# zigo_schem.net
KiCad netlist of a schematic drawn in Altium Designer
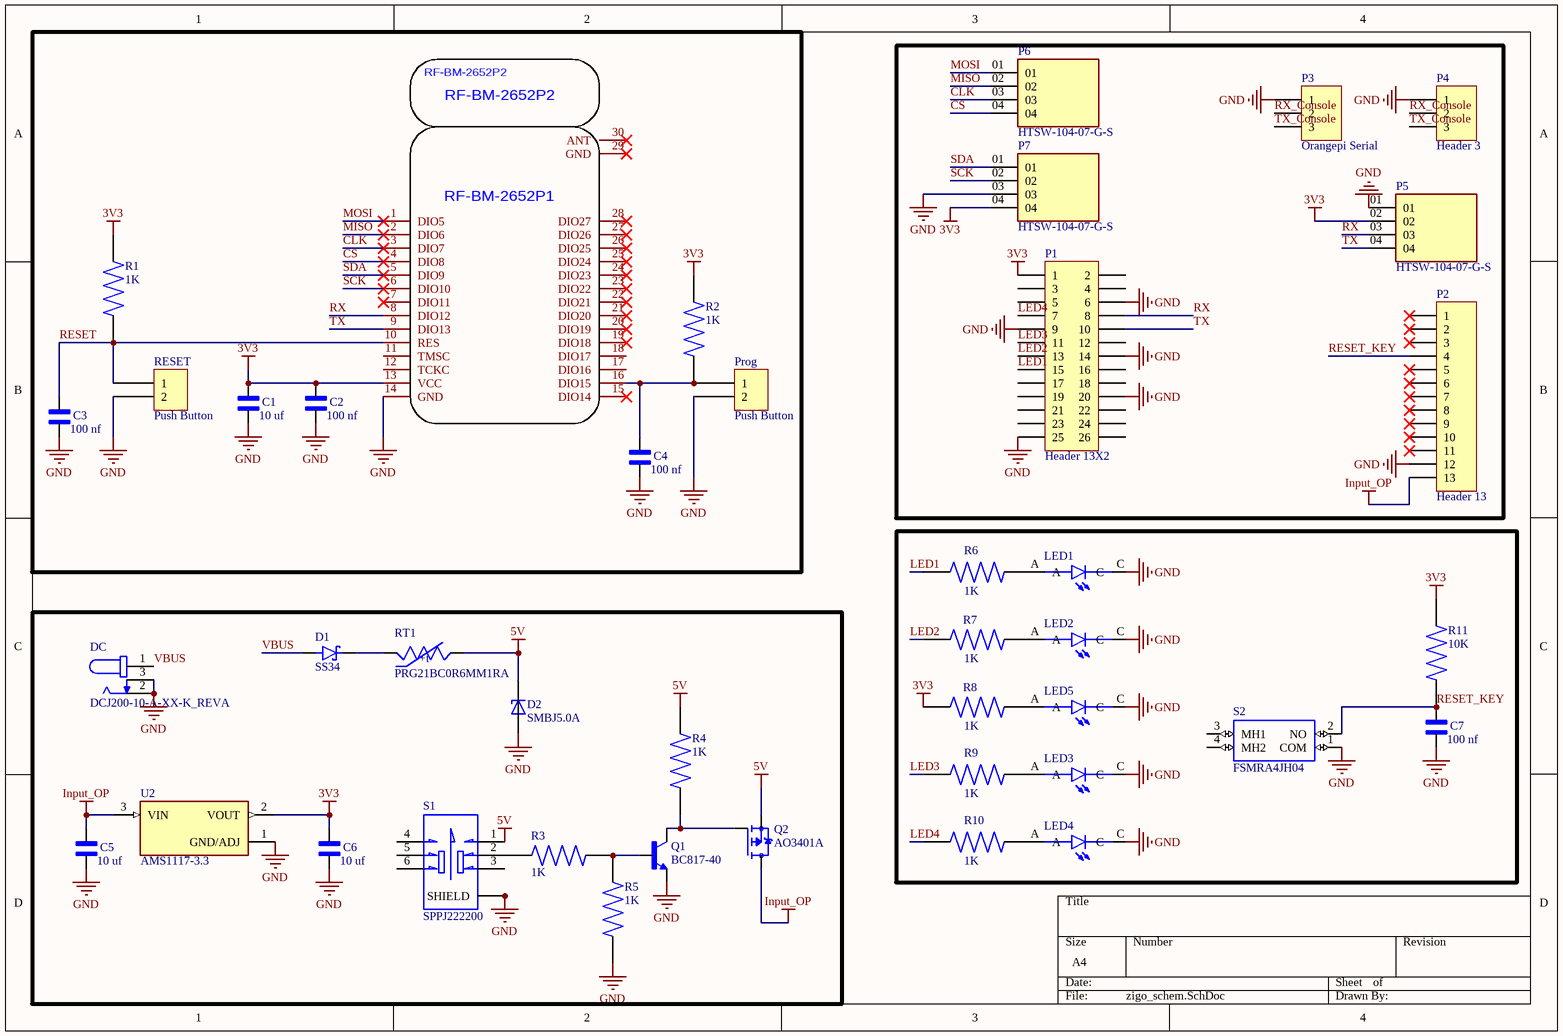
[diagram p0: zigo_schem.SchDoc]

(export (version "E")
  (design (tool "Eeschema 10.0.6"))
  (components
    (comp (ref "C1")
      (value "10 uf")
      (footprint "CAPC2012X90N")
      (description "Capacitor: ceramic; MLCC; 100nF; 25V; X7R; Â±10%; SMD; 0805")
      (fields (field (name "MF") "Vishay Vitramon") (field (name "MP") "VJ0805Y104KXXCW1BC"))
      (libsource (lib "Smart_InWall") (part "VJ0805Y104KXXCW1BC"))
    )
    (comp (ref "C2")
      (value "100 nf")
      (footprint "CAPC2012X90N")
      (description "Capacitor: ceramic; MLCC; 100nF; 25V; X7R; Â±10%; SMD; 0805")
      (fields (field (name "MF") "Vishay Vitramon") (field (name "MP") "VJ0805Y104KXXCW1BC"))
      (libsource (lib "Smart_InWall") (part "VJ0805Y104KXXCW1BC"))
    )
    (comp (ref "C3")
      (value "100 nf")
      (footprint "CAPC2012X90N")
      (description "Capacitor: ceramic; MLCC; 100nF; 25V; X7R; Â±10%; SMD; 0805")
      (fields (field (name "MF") "Vishay Vitramon") (field (name "MP") "VJ0805Y104KXXCW1BC"))
      (libsource (lib "Smart_InWall") (part "VJ0805Y104KXXCW1BC"))
    )
    (comp (ref "C4")
      (value "100 nf")
      (footprint "CAPC2012X90N")
      (description "Capacitor: ceramic; MLCC; 100nF; 25V; X7R; Â±10%; SMD; 0805")
      (fields (field (name "MF") "Vishay Vitramon") (field (name "MP") "VJ0805Y104KXXCW1BC"))
      (libsource (lib "Smart_InWall") (part "VJ0805Y104KXXCW1BC"))
    )
    (comp (ref "C5")
      (value "10 uf")
      (footprint "CAPC2012X90N")
      (description "Capacitor: ceramic; MLCC; 100nF; 25V; X7R; Â±10%; SMD; 0805")
      (fields (field (name "MF") "Vishay Vitramon") (field (name "MP") "VJ0805Y104KXXCW1BC"))
      (libsource (lib "Smart_InWall") (part "VJ0805Y104KXXCW1BC"))
    )
    (comp (ref "C6")
      (value "10 uf")
      (footprint "CAPC2012X90N")
      (description "Capacitor: ceramic; MLCC; 100nF; 25V; X7R; Â±10%; SMD; 0805")
      (fields (field (name "MF") "Vishay Vitramon") (field (name "MP") "VJ0805Y104KXXCW1BC"))
      (libsource (lib "Smart_InWall") (part "VJ0805Y104KXXCW1BC"))
    )
    (comp (ref "C7")
      (value "100 nf")
      (footprint "CAPC2012X90N")
      (description "Capacitor: ceramic; MLCC; 100nF; 25V; X7R; Â±10%; SMD; 0805")
      (fields (field (name "MF") "Vishay Vitramon") (field (name "MP") "VJ0805Y104KXXCW1BC"))
      (libsource (lib "Smart_InWall") (part "VJ0805Y104KXXCW1BC"))
    )
    (comp (ref "cc")
      (value "RF-BM-2652P2")
      (footprint "PCBComponent_1 - duplicate")
      (libsource (lib "zigbee_orangepi") (part "RF-BM-2652P2"))
    )
    (comp (ref "D1")
      (value "SS34")
      (footprint "DIOM7959X265N")
      (description "Diode Schottky 40 V 3A Surface Mount SMC (DO-214AB)")
      (fields (field (name "MF") "onsemi"))
      (libsource (lib "ZigbeeHub") (part "SS34"))
    )
    (comp (ref "D2")
      (value "SMBJ5.0A")
      (footprint "DIOM4336X265N")
      (description "600W, 6.7V, 5%, Unidirectional, TVS")
      (fields (field (name "MF") "Taiwan Semiconductor"))
      (libsource (lib "ZigbeeHub") (part "SMBJ5.0A"))
    )
    (comp (ref "DC")
      (value "DCJ200-10-A-XX-K_REVA")
      (footprint "GCT_DCJ200-10-A-XX-K_REVA")
      (description "Power Barrel Connector Jack 2.05mm ID (0.081), 5.50mm OD (0.217) Through Hole, Right Angle")
      (fields (field (name "MF") "Global Connector Technology") (field (name "MP") "DCJ200-10-A-K1-K"))
      (libsource (lib "ZigbeeHub") (part "DCJ200-10-A-XX-K_REVA"))
    )
    (comp (ref "LED1")
      (value "597-3305-607F")
      (footprint "LEDC2012X70N")
      (description "LED Uni-Color Green 4-Pin Chip 0805 T/R")
      (libsource (lib "597-3305-607F") (part "597-3305-607F"))
    )
    (comp (ref "LED2")
      (value "597-3305-607F")
      (footprint "LEDC2012X70N")
      (description "LED Uni-Color Green 4-Pin Chip 0805 T/R")
      (libsource (lib "597-3305-607F") (part "597-3305-607F"))
    )
    (comp (ref "LED3")
      (value "597-3305-607F")
      (footprint "LEDC2012X70N")
      (description "LED Uni-Color Green 4-Pin Chip 0805 T/R")
      (libsource (lib "597-3305-607F") (part "597-3305-607F"))
    )
    (comp (ref "LED4")
      (value "597-3305-607F")
      (footprint "LEDC2012X70N")
      (description "LED Uni-Color Green 4-Pin Chip 0805 T/R")
      (libsource (lib "597-3305-607F") (part "597-3305-607F"))
    )
    (comp (ref "LED5")
      (value "597-3305-607F")
      (footprint "LEDC2012X70N")
      (description "LED Uni-Color Green 4-Pin Chip 0805 T/R")
      (libsource (lib "597-3305-607F") (part "597-3305-607F"))
    )
    (comp (ref "P1")
      (value "Header 13X2")
      (footprint "HDR2X13")
      (description "Header, 13-Pin, Dual row")
      (fields (field (name "PUBLISHER") "Altium Limited"))
      (libsource (lib "zigbee_orangepi") (part "Header 13X2"))
    )
    (comp (ref "P2")
      (value "Header 13")
      (footprint "HDR1X13")
      (description "Header, 13-Pin")
      (fields (field (name "PUBLISHER") "Altium Limited"))
      (libsource (lib "zigbee_orangepi") (part "Header 13"))
    )
    (comp (ref "P3")
      (value "Orangepi Serial")
      (footprint "HDR1X3")
      (description "Header, 3-Pin")
      (fields (field (name "PUBLISHER") "Altium Limited"))
      (libsource (lib "zigbee_orangepi") (part "Header 3"))
    )
    (comp (ref "P4")
      (value "Header 3")
      (footprint "HDR1X3")
      (description "Header, 3-Pin")
      (fields (field (name "PUBLISHER") "Altium Limited"))
      (libsource (lib "zigbee_orangepi") (part "Header 3"))
    )
    (comp (ref "P5")
      (value "HTSW-104-07-G-S")
      (footprint "SAMTEC_HTSW-104-07-G-S")
      (libsource (lib "ZigbeeHub") (part "HTSW-104-07-G-S"))
    )
    (comp (ref "P6")
      (value "HTSW-104-07-G-S")
      (footprint "SAMTEC_HTSW-104-07-G-S")
      (libsource (lib "ZigbeeHub") (part "HTSW-104-07-G-S"))
    )
    (comp (ref "P7")
      (value "HTSW-104-07-G-S")
      (footprint "SAMTEC_HTSW-104-07-G-S")
      (libsource (lib "ZigbeeHub") (part "HTSW-104-07-G-S"))
    )
    (comp (ref "Prog")
      (value "Push Button")
      (footprint "Push Button")
      (libsource (lib "zigbee_orangepi") (part "Push Button"))
    )
    (comp (ref "Q1")
      (value "BC817-40")
      (footprint "SOT95P240X120-3N")
      (description "BJT, SOT-23, 45V, 800mA, NPN, 0.31W, 150Â°C")
      (fields (field (name "MF") "Diotec Semiconductor"))
      (libsource (lib "ZigbeeHub") (part "BC817-40"))
    )
    (comp (ref "Q2")
      (value "AO3401A")
      (footprint "SOT23-3")
      (description "P-Channel 30 V 4A (Ta) 1.4W (Ta) Surface Mount SOT-23-3")
      (fields (field (name "MF") "Alpha & Omega Semiconductor"))
      (libsource (lib "ZigbeeHub") (part "AO3401A"))
    )
    (comp (ref "R1")
      (value "1K")
      (footprint "RESC2012X65N")
      (description "RES SMD 5.11KOHM 0.1% 1/10W 0805")
      (fields (field (name "MF") "TE Connectivity") (field (name "MP") "RN73C2A5K11BTD"))
      (libsource (lib "Smart_InWall") (part "RN73C2A5K11BTD"))
    )
    (comp (ref "R2")
      (value "1K")
      (footprint "RESC2012X65N")
      (description "RES SMD 5.11KOHM 0.1% 1/10W 0805")
      (fields (field (name "MF") "TE Connectivity") (field (name "MP") "RN73C2A5K11BTD"))
      (libsource (lib "Smart_InWall") (part "RN73C2A5K11BTD"))
    )
    (comp (ref "R3")
      (value "1K")
      (footprint "RESC2012X65N")
      (description "RES SMD 5.11KOHM 0.1% 1/10W 0805")
      (fields (field (name "MF") "TE Connectivity") (field (name "MP") "RN73C2A5K11BTD"))
      (libsource (lib "Smart_InWall") (part "RN73C2A5K11BTD"))
    )
    (comp (ref "R4")
      (value "1K")
      (footprint "RESC2012X65N")
      (description "RES SMD 5.11KOHM 0.1% 1/10W 0805")
      (fields (field (name "MF") "TE Connectivity") (field (name "MP") "RN73C2A5K11BTD"))
      (libsource (lib "Smart_InWall") (part "RN73C2A5K11BTD"))
    )
    (comp (ref "R5")
      (value "1K")
      (footprint "RESC2012X65N")
      (description "RES SMD 5.11KOHM 0.1% 1/10W 0805")
      (fields (field (name "MF") "TE Connectivity") (field (name "MP") "RN73C2A5K11BTD"))
      (libsource (lib "Smart_InWall") (part "RN73C2A5K11BTD"))
    )
    (comp (ref "R6")
      (value "1K")
      (footprint "RESC2012X65N")
      (description "RES SMD 5.11KOHM 0.1% 1/10W 0805")
      (fields (field (name "MF") "TE Connectivity") (field (name "MP") "RN73C2A5K11BTD"))
      (libsource (lib "Smart_InWall") (part "RN73C2A5K11BTD"))
    )
    (comp (ref "R7")
      (value "1K")
      (footprint "RESC2012X65N")
      (description "RES SMD 5.11KOHM 0.1% 1/10W 0805")
      (fields (field (name "MF") "TE Connectivity") (field (name "MP") "RN73C2A5K11BTD"))
      (libsource (lib "Smart_InWall") (part "RN73C2A5K11BTD"))
    )
    (comp (ref "R8")
      (value "1K")
      (footprint "RESC2012X65N")
      (description "RES SMD 5.11KOHM 0.1% 1/10W 0805")
      (fields (field (name "MF") "TE Connectivity") (field (name "MP") "RN73C2A5K11BTD"))
      (libsource (lib "Smart_InWall") (part "RN73C2A5K11BTD"))
    )
    (comp (ref "R9")
      (value "1K")
      (footprint "RESC2012X65N")
      (description "RES SMD 5.11KOHM 0.1% 1/10W 0805")
      (fields (field (name "MF") "TE Connectivity") (field (name "MP") "RN73C2A5K11BTD"))
      (libsource (lib "Smart_InWall") (part "RN73C2A5K11BTD"))
    )
    (comp (ref "R10")
      (value "1K")
      (footprint "RESC2012X65N")
      (description "RES SMD 5.11KOHM 0.1% 1/10W 0805")
      (fields (field (name "MF") "TE Connectivity") (field (name "MP") "RN73C2A5K11BTD"))
      (libsource (lib "Smart_InWall") (part "RN73C2A5K11BTD"))
    )
    (comp (ref "R11")
      (value "10K")
      (footprint "RESC2012X65N")
      (description "RES SMD 5.11KOHM 0.1% 1/10W 0805")
      (fields (field (name "MF") "TE Connectivity") (field (name "MP") "RN73C2A5K11BTD"))
      (libsource (lib "Smart_InWall") (part "RN73C2A5K11BTD"))
    )
    (comp (ref "RESET")
      (value "Push Button")
      (footprint "Push Button")
      (libsource (lib "zigbee_orangepi") (part "Push Button"))
    )
    (comp (ref "RT1")
      (value "PRG21BC0R6MM1RA")
      (footprint "THRMC2012X110N")
      (libsource (lib "ZigbeeHub") (part "PRG21BC0R6MM1RA"))
    )
    (comp (ref "S1")
      (value "SPPJ222200")
      (footprint "ZigbeeHub:SW_SPPJ222200")
      (fields (field (name "MF") "ALPS"))
      (libsource (lib "ZigbeeHub") (part "SPPJ222200"))
    )
    (comp (ref "S2")
      (value "FSMRA4JH04")
      (footprint "FSMRA4JH04")
      (description "Switch, Pushbutton, Tactile, Single Pole, 50mA, Right Angle")
      (fields (field (name "MF") "TE Connectivity"))
      (libsource (lib "zigbee_orangepi") (part "FSMRA4JH04"))
    )
    (comp (ref "U2")
      (value "AMS1117-3.3")
      (footprint "SOT229P700X180-4N")
      (description "Sot223/Pkg 1-Amp 3.3-Volt Low Drop Out Voltage Regulatator")
      (fields (field (name "MF") "Advanced Monolithic Systems"))
      (libsource (lib "ZigbeeHub") (part "AMS1117-3.3"))
    )
  )
  (nets
    (net (code "2") (name "/CLK") (class "Default")
      (node (ref "P6") (pin "03") (pinfunction "03_03") (pintype "passive"))
      (node (ref "cc") (pin "3") (pinfunction "DIO7_3") (pintype "passive"))
    )
    (net (code "3") (name "/CS") (class "Default")
      (node (ref "P6") (pin "04") (pinfunction "04_04") (pintype "passive"))
      (node (ref "cc") (pin "4") (pinfunction "DIO8_4") (pintype "passive"))
    )
    (net (code "4") (name "/LED1") (class "Default")
      (node (ref "P1") (pin "15") (pinfunction "15_15") (pintype "passive"))
      (node (ref "R6") (pin "1") (pinfunction "1_1") (pintype "passive"))
    )
    (net (code "5") (name "/LED2") (class "Default")
      (node (ref "P1") (pin "13") (pinfunction "13_13") (pintype "passive"))
      (node (ref "R7") (pin "1") (pinfunction "1_1") (pintype "passive"))
    )
    (net (code "6") (name "/LED3") (class "Default")
      (node (ref "P1") (pin "11") (pinfunction "11_11") (pintype "passive"))
      (node (ref "R9") (pin "1") (pinfunction "1_1") (pintype "passive"))
    )
    (net (code "7") (name "/LED4") (class "Default")
      (node (ref "P1") (pin "7") (pinfunction "7_7") (pintype "passive"))
      (node (ref "R10") (pin "1") (pinfunction "1_1") (pintype "passive"))
    )
    (net (code "8") (name "/MISO") (class "Default")
      (node (ref "P6") (pin "02") (pinfunction "02_02") (pintype "passive"))
      (node (ref "cc") (pin "2") (pinfunction "DIO6_2") (pintype "passive"))
    )
    (net (code "9") (name "/MOSI") (class "Default")
      (node (ref "P6") (pin "01") (pinfunction "01_01") (pintype "passive"))
      (node (ref "cc") (pin "1") (pinfunction "DIO5_1") (pintype "passive"))
    )
    (net (code "10") (name "/RESET") (class "Default")
      (node (ref "C3") (pin "2") (pinfunction "2_2") (pintype "passive"))
      (node (ref "R1") (pin "1") (pinfunction "1_1") (pintype "passive"))
      (node (ref "RESET") (pin "1") (pinfunction "1_1") (pintype "passive"))
      (node (ref "cc") (pin "10") (pinfunction "RES_10") (pintype "passive"))
    )
    (net (code "11") (name "/RESET_KEY") (class "Default")
      (node (ref "C7") (pin "2") (pinfunction "2_2") (pintype "passive"))
      (node (ref "P2") (pin "4") (pinfunction "4_4") (pintype "passive"))
      (node (ref "R11") (pin "1") (pinfunction "1_1") (pintype "passive"))
      (node (ref "S2") (pin "2") (pinfunction "NO_2") (pintype "bidirectional"))
    )
    (net (code "12") (name "/RX") (class "Default")
      (node (ref "P1") (pin "8") (pinfunction "8_8") (pintype "passive"))
      (node (ref "P5") (pin "03") (pinfunction "03_03") (pintype "passive"))
      (node (ref "cc") (pin "8") (pinfunction "DIO12_8") (pintype "passive"))
    )
    (net (code "13") (name "/RX_Console") (class "Default")
      (node (ref "P3") (pin "2") (pinfunction "2_2") (pintype "passive"))
      (node (ref "P4") (pin "2") (pinfunction "2_2") (pintype "passive"))
    )
    (net (code "14") (name "/SCK") (class "Default")
      (node (ref "P7") (pin "02") (pinfunction "02_02") (pintype "passive"))
      (node (ref "cc") (pin "6") (pinfunction "DIO10_6") (pintype "passive"))
    )
    (net (code "15") (name "/SDA") (class "Default")
      (node (ref "P7") (pin "01") (pinfunction "01_01") (pintype "passive"))
      (node (ref "cc") (pin "5") (pinfunction "DIO9_5") (pintype "passive"))
    )
    (net (code "16") (name "/TX") (class "Default")
      (node (ref "P1") (pin "10") (pinfunction "10_10") (pintype "passive"))
      (node (ref "P5") (pin "04") (pinfunction "04_04") (pintype "passive"))
      (node (ref "cc") (pin "9") (pinfunction "DIO13_9") (pintype "passive"))
    )
    (net (code "17") (name "/TX_Console") (class "Default")
      (node (ref "P3") (pin "3") (pinfunction "3_3") (pintype "passive"))
      (node (ref "P4") (pin "3") (pinfunction "3_3") (pintype "passive"))
    )
    (net (code "18") (name "/VBUS") (class "Default")
      (node (ref "D1") (pin "A") (pinfunction "A_A") (pintype "passive"))
      (node (ref "DC") (pin "1") (pinfunction "1_1") (pintype "passive"))
    )
    (net (code "19") (name "3V3") (class "Default")
      (node (ref "C1") (pin "2") (pinfunction "2_2") (pintype "passive"))
      (node (ref "C2") (pin "2") (pinfunction "2_2") (pintype "passive"))
      (node (ref "C6") (pin "2") (pinfunction "2_2") (pintype "passive"))
      (node (ref "P1") (pin "1") (pinfunction "1_1") (pintype "passive"))
      (node (ref "P5") (pin "02") (pinfunction "02_02") (pintype "passive"))
      (node (ref "P7") (pin "04") (pinfunction "04_04") (pintype "passive"))
      (node (ref "R1") (pin "2") (pinfunction "2_2") (pintype "passive"))
      (node (ref "R11") (pin "2") (pinfunction "2_2") (pintype "passive"))
      (node (ref "R2") (pin "2") (pinfunction "2_2") (pintype "passive"))
      (node (ref "R8") (pin "1") (pinfunction "1_1") (pintype "passive"))
      (node (ref "U2") (pin "2") (pinfunction "VOUT_2") (pintype "output"))
      (node (ref "cc") (pin "13") (pinfunction "VCC_13") (pintype "passive"))
    )
    (net (code "20") (name "5V") (class "Default")
      (node (ref "D2") (pin "C") (pinfunction "C_C") (pintype "passive"))
      (node (ref "Q2") (pin "2") (pinfunction "S_2") (pintype "passive"))
      (node (ref "R4") (pin "1") (pinfunction "1_1") (pintype "passive"))
      (node (ref "RT1") (pin "2") (pinfunction "2_2") (pintype "passive"))
      (node (ref "S1") (pin "1") (pinfunction "1_1") (pintype "passive"))
    )
    (net (code "21") (name "GND") (class "Default")
      (node (ref "C1") (pin "1") (pinfunction "1_1") (pintype "passive"))
      (node (ref "C2") (pin "1") (pinfunction "1_1") (pintype "passive"))
      (node (ref "C3") (pin "1") (pinfunction "1_1") (pintype "passive"))
      (node (ref "C4") (pin "1") (pinfunction "1_1") (pintype "passive"))
      (node (ref "C5") (pin "1") (pinfunction "1_1") (pintype "passive"))
      (node (ref "C6") (pin "1") (pinfunction "1_1") (pintype "passive"))
      (node (ref "C7") (pin "1") (pinfunction "1_1") (pintype "passive"))
      (node (ref "D2") (pin "A") (pinfunction "A_A") (pintype "passive"))
      (node (ref "DC") (pin "2") (pinfunction "2_2") (pintype "passive"))
      (node (ref "DC") (pin "3") (pinfunction "3_3") (pintype "passive"))
      (node (ref "LED1") (pin "C") (pinfunction "C_C") (pintype "passive"))
      (node (ref "LED2") (pin "C") (pinfunction "C_C") (pintype "passive"))
      (node (ref "LED3") (pin "C") (pinfunction "C_C") (pintype "passive"))
      (node (ref "LED4") (pin "C") (pinfunction "C_C") (pintype "passive"))
      (node (ref "LED5") (pin "C") (pinfunction "C_C") (pintype "passive"))
      (node (ref "P1") (pin "14") (pinfunction "14_14") (pintype "passive"))
      (node (ref "P1") (pin "20") (pinfunction "20_20") (pintype "passive"))
      (node (ref "P1") (pin "25") (pinfunction "25_25") (pintype "passive"))
      (node (ref "P1") (pin "6") (pinfunction "6_6") (pintype "passive"))
      (node (ref "P1") (pin "9") (pinfunction "9_9") (pintype "passive"))
      (node (ref "P2") (pin "12") (pinfunction "12_12") (pintype "passive"))
      (node (ref "P3") (pin "1") (pinfunction "1_1") (pintype "passive"))
      (node (ref "P4") (pin "1") (pinfunction "1_1") (pintype "passive"))
      (node (ref "P5") (pin "01") (pinfunction "01_01") (pintype "passive"))
      (node (ref "P7") (pin "03") (pinfunction "03_03") (pintype "passive"))
      (node (ref "Prog") (pin "2") (pinfunction "2_2") (pintype "passive"))
      (node (ref "Q1") (pin "2") (pinfunction "E_2") (pintype "passive"))
      (node (ref "R5") (pin "2") (pinfunction "2_2") (pintype "passive"))
      (node (ref "RESET") (pin "2") (pinfunction "2_2") (pintype "passive"))
      (node (ref "S1") (pin "S1") (pinfunction "SHIELD_S1") (pintype "passive"))
      (node (ref "S1") (pin "S2") (pinfunction "SHIELD_S2") (pintype "passive"))
      (node (ref "S2") (pin "1") (pinfunction "COM_1") (pintype "bidirectional"))
      (node (ref "U2") (pin "1") (pinfunction "GND/ADJ_1") (pintype "power_in"))
      (node (ref "cc") (pin "14") (pinfunction "GND_14") (pintype "passive"))
    )
    (net (code "22") (name "Input_OP") (class "Default")
      (node (ref "C5") (pin "2") (pinfunction "2_2") (pintype "passive"))
      (node (ref "P2") (pin "13") (pinfunction "13_13") (pintype "passive"))
      (node (ref "Q2") (pin "3") (pinfunction "D_3") (pintype "passive"))
      (node (ref "U2") (pin "3") (pinfunction "VIN_3") (pintype "input"))
    )
    (net (code "23") (name "Net-(D1-K)") (class "Default")
      (node (ref "D1") (pin "C") (pinfunction "K_C") (pintype "passive"))
      (node (ref "RT1") (pin "1") (pinfunction "1_1") (pintype "passive"))
    )
    (net (code "24") (name "Net-(LED1-PadA)") (class "Default")
      (node (ref "LED1") (pin "A") (pinfunction "A_A") (pintype "passive"))
      (node (ref "R6") (pin "2") (pinfunction "2_2") (pintype "passive"))
    )
    (net (code "25") (name "Net-(LED2-PadA)") (class "Default")
      (node (ref "LED2") (pin "A") (pinfunction "A_A") (pintype "passive"))
      (node (ref "R7") (pin "2") (pinfunction "2_2") (pintype "passive"))
    )
    (net (code "26") (name "Net-(LED3-PadA)") (class "Default")
      (node (ref "LED3") (pin "A") (pinfunction "A_A") (pintype "passive"))
      (node (ref "R9") (pin "2") (pinfunction "2_2") (pintype "passive"))
    )
    (net (code "27") (name "Net-(LED4-PadA)") (class "Default")
      (node (ref "LED4") (pin "A") (pinfunction "A_A") (pintype "passive"))
      (node (ref "R10") (pin "2") (pinfunction "2_2") (pintype "passive"))
    )
    (net (code "28") (name "Net-(LED5-PadA)") (class "Default")
      (node (ref "LED5") (pin "A") (pinfunction "A_A") (pintype "passive"))
      (node (ref "R8") (pin "2") (pinfunction "2_2") (pintype "passive"))
    )
    (net (code "29") (name "Net-(Q1-B)") (class "Default")
      (node (ref "Q1") (pin "1") (pinfunction "B_1") (pintype "passive"))
      (node (ref "R3") (pin "1") (pinfunction "1_1") (pintype "passive"))
      (node (ref "R5") (pin "1") (pinfunction "1_1") (pintype "passive"))
    )
    (net (code "30") (name "Net-(Q1-C)") (class "Default")
      (node (ref "Q1") (pin "3") (pinfunction "C_3") (pintype "passive"))
      (node (ref "Q2") (pin "1") (pinfunction "G_1") (pintype "passive"))
      (node (ref "R4") (pin "2") (pinfunction "2_2") (pintype "passive"))
    )
    (net (code "31") (name "Net-(R3-Pad2)") (class "Default")
      (node (ref "R3") (pin "2") (pinfunction "2_2") (pintype "passive"))
      (node (ref "S1") (pin "2") (pinfunction "2_2") (pintype "passive"))
    )
    (net (code "32") (name "Net-(cc-DIO15)") (class "Default")
      (node (ref "C4") (pin "2") (pinfunction "2_2") (pintype "passive"))
      (node (ref "Prog") (pin "1") (pinfunction "1_1") (pintype "passive"))
      (node (ref "R2") (pin "1") (pinfunction "1_1") (pintype "passive"))
      (node (ref "cc") (pin "16") (pinfunction "DIO15_16") (pintype "passive"))
    )
    (net (code "33") (name "unconnected-(P1-Pad2)") (class "Default")
      (node (ref "P1") (pin "2") (pinfunction "2_2") (pintype "passive"))
    )
    (net (code "34") (name "unconnected-(P1-Pad3)") (class "Default")
      (node (ref "P1") (pin "3") (pinfunction "3_3") (pintype "passive"))
    )
    (net (code "35") (name "unconnected-(P1-Pad4)") (class "Default")
      (node (ref "P1") (pin "4") (pinfunction "4_4") (pintype "passive"))
    )
    (net (code "36") (name "unconnected-(P1-Pad5)") (class "Default")
      (node (ref "P1") (pin "5") (pinfunction "5_5") (pintype "passive"))
    )
    (net (code "37") (name "unconnected-(P1-Pad12)") (class "Default")
      (node (ref "P1") (pin "12") (pinfunction "12_12") (pintype "passive"))
    )
    (net (code "38") (name "unconnected-(P1-Pad16)") (class "Default")
      (node (ref "P1") (pin "16") (pinfunction "16_16") (pintype "passive"))
    )
    (net (code "39") (name "unconnected-(P1-Pad17)") (class "Default")
      (node (ref "P1") (pin "17") (pinfunction "17_17") (pintype "passive"))
    )
    (net (code "40") (name "unconnected-(P1-Pad18)") (class "Default")
      (node (ref "P1") (pin "18") (pinfunction "18_18") (pintype "passive"))
    )
    (net (code "41") (name "unconnected-(P1-Pad19)") (class "Default")
      (node (ref "P1") (pin "19") (pinfunction "19_19") (pintype "passive"))
    )
    (net (code "42") (name "unconnected-(P1-Pad21)") (class "Default")
      (node (ref "P1") (pin "21") (pinfunction "21_21") (pintype "passive"))
    )
    (net (code "43") (name "unconnected-(P1-Pad22)") (class "Default")
      (node (ref "P1") (pin "22") (pinfunction "22_22") (pintype "passive"))
    )
    (net (code "44") (name "unconnected-(P1-Pad23)") (class "Default")
      (node (ref "P1") (pin "23") (pinfunction "23_23") (pintype "passive"))
    )
    (net (code "45") (name "unconnected-(P1-Pad24)") (class "Default")
      (node (ref "P1") (pin "24") (pinfunction "24_24") (pintype "passive"))
    )
    (net (code "46") (name "unconnected-(P1-Pad26)") (class "Default")
      (node (ref "P1") (pin "26") (pinfunction "26_26") (pintype "passive"))
    )
    (net (code "47") (name "unconnected-(P2-Pad1)") (class "Default")
      (node (ref "P2") (pin "1") (pinfunction "1_1") (pintype "passive+no_connect"))
    )
    (net (code "48") (name "unconnected-(P2-Pad2)") (class "Default")
      (node (ref "P2") (pin "2") (pinfunction "2_2") (pintype "passive+no_connect"))
    )
    (net (code "49") (name "unconnected-(P2-Pad3)") (class "Default")
      (node (ref "P2") (pin "3") (pinfunction "3_3") (pintype "passive+no_connect"))
    )
    (net (code "50") (name "unconnected-(P2-Pad5)") (class "Default")
      (node (ref "P2") (pin "5") (pinfunction "5_5") (pintype "passive+no_connect"))
    )
    (net (code "51") (name "unconnected-(P2-Pad6)") (class "Default")
      (node (ref "P2") (pin "6") (pinfunction "6_6") (pintype "passive+no_connect"))
    )
    (net (code "52") (name "unconnected-(P2-Pad7)") (class "Default")
      (node (ref "P2") (pin "7") (pinfunction "7_7") (pintype "passive+no_connect"))
    )
    (net (code "53") (name "unconnected-(P2-Pad8)") (class "Default")
      (node (ref "P2") (pin "8") (pinfunction "8_8") (pintype "passive+no_connect"))
    )
    (net (code "54") (name "unconnected-(P2-Pad9)") (class "Default")
      (node (ref "P2") (pin "9") (pinfunction "9_9") (pintype "passive+no_connect"))
    )
    (net (code "55") (name "unconnected-(P2-Pad10)") (class "Default")
      (node (ref "P2") (pin "10") (pinfunction "10_10") (pintype "passive+no_connect"))
    )
    (net (code "56") (name "unconnected-(P2-Pad11)") (class "Default")
      (node (ref "P2") (pin "11") (pinfunction "11_11") (pintype "passive+no_connect"))
    )
    (net (code "57") (name "unconnected-(S1-Pad3)") (class "Default")
      (node (ref "S1") (pin "3") (pinfunction "3_3") (pintype "passive"))
    )
    (net (code "58") (name "unconnected-(S1-Pad4)") (class "Default")
      (node (ref "S1") (pin "4") (pinfunction "4_4") (pintype "passive"))
    )
    (net (code "59") (name "unconnected-(S1-Pad5)") (class "Default")
      (node (ref "S1") (pin "5") (pinfunction "5_5") (pintype "passive"))
    )
    (net (code "60") (name "unconnected-(S1-Pad6)") (class "Default")
      (node (ref "S1") (pin "6") (pinfunction "6_6") (pintype "passive"))
    )
    (net (code "61") (name "unconnected-(S2-MH1-Pad3)") (class "Default")
      (node (ref "S2") (pin "3") (pinfunction "MH1_3") (pintype "bidirectional"))
    )
    (net (code "62") (name "unconnected-(S2-MH2-Pad4)") (class "Default")
      (node (ref "S2") (pin "4") (pinfunction "MH2_4") (pintype "bidirectional"))
    )
    (net (code "63") (name "unconnected-(cc-ANT-Pad30)") (class "Default")
      (node (ref "cc") (pin "30") (pinfunction "ANT_30") (pintype "passive+no_connect"))
    )
    (net (code "64") (name "unconnected-(cc-DIO11-Pad7)") (class "Default")
      (node (ref "cc") (pin "7") (pinfunction "DIO11_7") (pintype "passive+no_connect"))
    )
    (net (code "65") (name "unconnected-(cc-DIO14-Pad15)") (class "Default")
      (node (ref "cc") (pin "15") (pinfunction "DIO14_15") (pintype "passive+no_connect"))
    )
    (net (code "66") (name "unconnected-(cc-DIO16-Pad17)") (class "Default")
      (node (ref "cc") (pin "17") (pinfunction "DIO16_17") (pintype "passive"))
    )
    (net (code "67") (name "unconnected-(cc-DIO17-Pad18)") (class "Default")
      (node (ref "cc") (pin "18") (pinfunction "DIO17_18") (pintype "passive"))
    )
    (net (code "68") (name "unconnected-(cc-DIO18-Pad19)") (class "Default")
      (node (ref "cc") (pin "19") (pinfunction "DIO18_19") (pintype "passive+no_connect"))
    )
    (net (code "69") (name "unconnected-(cc-DIO19-Pad20)") (class "Default")
      (node (ref "cc") (pin "20") (pinfunction "DIO19_20") (pintype "passive+no_connect"))
    )
    (net (code "70") (name "unconnected-(cc-DIO20-Pad21)") (class "Default")
      (node (ref "cc") (pin "21") (pinfunction "DIO20_21") (pintype "passive+no_connect"))
    )
    (net (code "71") (name "unconnected-(cc-DIO21-Pad22)") (class "Default")
      (node (ref "cc") (pin "22") (pinfunction "DIO21_22") (pintype "passive+no_connect"))
    )
    (net (code "72") (name "unconnected-(cc-DIO22-Pad23)") (class "Default")
      (node (ref "cc") (pin "23") (pinfunction "DIO22_23") (pintype "passive+no_connect"))
    )
    (net (code "73") (name "unconnected-(cc-DIO23-Pad24)") (class "Default")
      (node (ref "cc") (pin "24") (pinfunction "DIO23_24") (pintype "passive+no_connect"))
    )
    (net (code "74") (name "unconnected-(cc-DIO24-Pad25)") (class "Default")
      (node (ref "cc") (pin "25") (pinfunction "DIO24_25") (pintype "passive+no_connect"))
    )
    (net (code "75") (name "unconnected-(cc-DIO25-Pad26)") (class "Default")
      (node (ref "cc") (pin "26") (pinfunction "DIO25_26") (pintype "passive+no_connect"))
    )
    (net (code "76") (name "unconnected-(cc-DIO26-Pad27)") (class "Default")
      (node (ref "cc") (pin "27") (pinfunction "DIO26_27") (pintype "passive+no_connect"))
    )
    (net (code "77") (name "unconnected-(cc-DIO27-Pad28)") (class "Default")
      (node (ref "cc") (pin "28") (pinfunction "DIO27_28") (pintype "passive+no_connect"))
    )
    (net (code "78") (name "unconnected-(cc-GND-Pad29)") (class "Default")
      (node (ref "cc") (pin "29") (pinfunction "GND_29") (pintype "passive+no_connect"))
    )
    (net (code "79") (name "unconnected-(cc-TCKC-Pad12)") (class "Default")
      (node (ref "cc") (pin "12") (pinfunction "TCKC_12") (pintype "passive"))
    )
    (net (code "80") (name "unconnected-(cc-TMSC-Pad11)") (class "Default")
      (node (ref "cc") (pin "11") (pinfunction "TMSC_11") (pintype "passive"))
    )
  )
)
